# stepper_counter.net
KiCad netlist of a schematic drawn in EAGLE
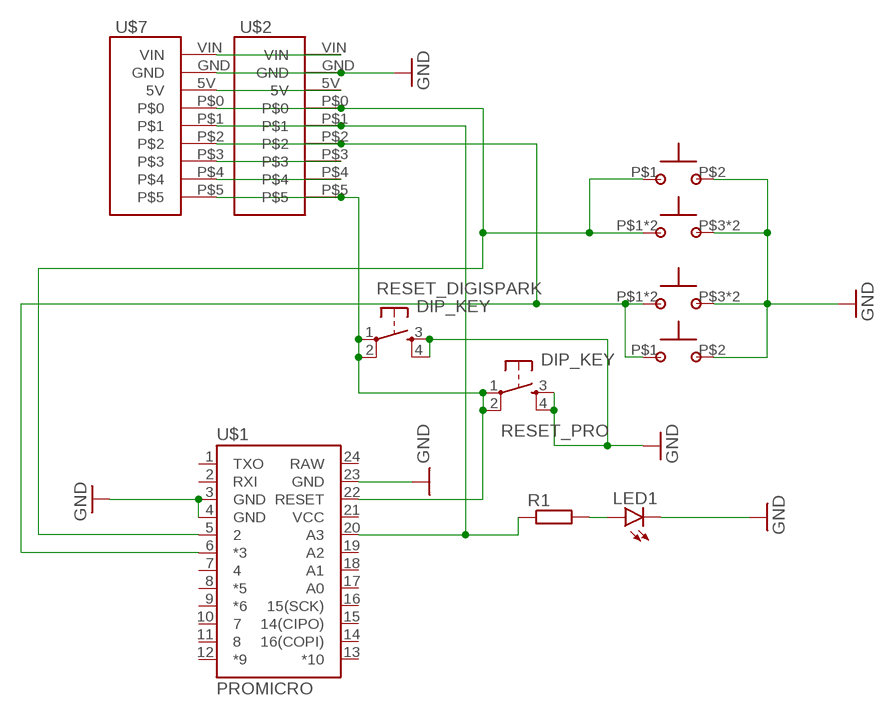
[diagram p0: schematic, sheet 1]

(export (version "E")
  (design (tool "Eeschema 10.0.6"))
  (components
    (comp (ref "LED1")
      (value "LED3MM")
      (footprint "eagle-import:LED3MM")
      (libsource (lib "eagle-import") (part "LED3MM"))
    )
    (comp (ref "R1")
      (value "R-EU_0207/10")
      (footprint "eagle-import:0207_10")
      (libsource (lib "eagle-import") (part "R-EU_0207/10"))
    )
    (comp (ref "RESET_DIGISPARK")
      (value "DIP_KEY")
      (footprint "eagle-import:B3F-10XX")
      (libsource (lib "eagle-import") (part "DIP_KEY"))
    )
    (comp (ref "RESET_PRO")
      (value "DIP_KEY")
      (footprint "eagle-import:B3F-10XX")
      (libsource (lib "eagle-import") (part "DIP_KEY"))
    )
    (comp (ref "U$1")
      (value "PROMICRO")
      (footprint "eagle-import:SPARKFUN_PRO_MICRO")
      (libsource (lib "eagle-import") (part "PROMICRO"))
    )
    (comp (ref "U$2")
      (value "DIGISPARK")
      (footprint "eagle-import:DIGISPARK")
      (libsource (lib "eagle-import") (part "DIGISPARK"))
    )
    (comp (ref "U$3")
      (value "RBS040210")
      (footprint "eagle-import:RBS040210")
      (libsource (lib "eagle-import") (part "RBS040210"))
    )
    (comp (ref "U$4")
      (value "RBS040210")
      (footprint "eagle-import:RBS040210")
      (libsource (lib "eagle-import") (part "RBS040210"))
    )
    (comp (ref "U$5")
      (value "SW20D")
      (footprint "eagle-import:SW20D")
      (libsource (lib "eagle-import") (part "SW20D"))
    )
    (comp (ref "U$6")
      (value "SW20D")
      (footprint "eagle-import:SW20D")
      (libsource (lib "eagle-import") (part "SW20D"))
    )
    (comp (ref "U$7")
      (value "DIGISPARK_USB")
      (footprint "eagle-import:DIGISPARK_USB")
      (libsource (lib "eagle-import") (part "DIGISPARK_USB"))
    )
  )
  (nets
    (net (code "1") (name "/RAW") (class "Default")
      (node (ref "U$1") (pin "24") (pinfunction "RAW_24") (pintype "power_in"))
    )
    (net (code "2") (name "/VCC") (class "Default")
      (node (ref "U$1") (pin "21") (pinfunction "VCC_21") (pintype "power_in"))
    )
    (net (code "3") (name "GND") (class "Default")
      (node (ref "LED1") (pin "K") (pinfunction "C_K") (pintype "passive"))
      (node (ref "RESET_DIGISPARK") (pin "3") (pinfunction "S_3") (pintype "passive"))
      (node (ref "RESET_DIGISPARK") (pin "4") (pinfunction "S1_4") (pintype "passive"))
      (node (ref "RESET_PRO") (pin "3") (pinfunction "S_3") (pintype "passive"))
      (node (ref "RESET_PRO") (pin "4") (pinfunction "S1_4") (pintype "passive"))
      (node (ref "U$1") (pin "23") (pinfunction "GND_23") (pintype "power_in"))
      (node (ref "U$1") (pin "3") (pinfunction "GND_3") (pintype "power_in"))
      (node (ref "U$1") (pin "4") (pinfunction "GND_4") (pintype "power_in"))
      (node (ref "U$2") (pin "GND") (pinfunction "GND_GND") (pintype "bidirectional"))
      (node (ref "U$3") (pin "P$3") (pinfunction "P$2_P$3") (pintype "bidirectional"))
      (node (ref "U$3") (pin "P$4") (pinfunction "P$2_P$4") (pintype "bidirectional"))
      (node (ref "U$4") (pin "P$3") (pinfunction "P$2_P$3") (pintype "bidirectional"))
      (node (ref "U$4") (pin "P$4") (pinfunction "P$2_P$4") (pintype "bidirectional"))
      (node (ref "U$5") (pin "P$2") (pinfunction "P$2_P$2") (pintype "bidirectional"))
      (node (ref "U$6") (pin "P$2") (pinfunction "P$2_P$2") (pintype "bidirectional"))
      (node (ref "U$7") (pin "GND") (pinfunction "GND_GND") (pintype "bidirectional"))
    )
    (net (code "4") (name "Net-(LED1-PadA)") (class "Default")
      (node (ref "LED1") (pin "A") (pinfunction "A_A") (pintype "passive"))
      (node (ref "R1") (pin "2") (pinfunction "2_2") (pintype "passive"))
    )
    (net (code "5") (name "Net-(RESET_DIGISPARK-P)") (class "Default")
      (node (ref "RESET_DIGISPARK") (pin "1") (pinfunction "P_1") (pintype "passive"))
      (node (ref "RESET_DIGISPARK") (pin "2") (pinfunction "P1_2") (pintype "passive"))
      (node (ref "RESET_PRO") (pin "1") (pinfunction "P_1") (pintype "passive"))
      (node (ref "RESET_PRO") (pin "2") (pinfunction "P1_2") (pintype "passive"))
      (node (ref "U$1") (pin "22") (pinfunction "RESET_22") (pintype "bidirectional"))
      (node (ref "U$2") (pin "P$5") (pinfunction "P$5_P$5") (pintype "bidirectional"))
      (node (ref "U$7") (pin "P$5") (pinfunction "P$5_P$5") (pintype "bidirectional"))
    )
    (net (code "6") (name "Net-(U$1-*3)") (class "Default")
      (node (ref "U$1") (pin "6") (pinfunction "*3_6") (pintype "bidirectional"))
      (node (ref "U$2") (pin "P$2") (pinfunction "P$2_P$2") (pintype "bidirectional"))
      (node (ref "U$4") (pin "P$1") (pinfunction "P$1_P$1") (pintype "bidirectional"))
      (node (ref "U$4") (pin "P$2") (pinfunction "P$1_P$2") (pintype "bidirectional"))
      (node (ref "U$6") (pin "P$1") (pinfunction "P$1_P$1") (pintype "bidirectional"))
      (node (ref "U$7") (pin "P$2") (pinfunction "P$2_P$2") (pintype "bidirectional"))
    )
    (net (code "7") (name "Net-(U$1-2)") (class "Default")
      (node (ref "U$1") (pin "5") (pinfunction "2_5") (pintype "bidirectional"))
      (node (ref "U$2") (pin "P$0") (pinfunction "P$0_P$0") (pintype "bidirectional"))
      (node (ref "U$3") (pin "P$1") (pinfunction "P$1_P$1") (pintype "bidirectional"))
      (node (ref "U$3") (pin "P$2") (pinfunction "P$1_P$2") (pintype "bidirectional"))
      (node (ref "U$5") (pin "P$1") (pinfunction "P$1_P$1") (pintype "bidirectional"))
      (node (ref "U$7") (pin "P$0") (pinfunction "P$0_P$0") (pintype "bidirectional"))
    )
    (net (code "8") (name "Net-(U$1-A3)") (class "Default")
      (node (ref "R1") (pin "1") (pinfunction "1_1") (pintype "passive"))
      (node (ref "U$1") (pin "20") (pinfunction "A3_20") (pintype "bidirectional"))
      (node (ref "U$2") (pin "P$1") (pinfunction "P$1_P$1") (pintype "bidirectional"))
      (node (ref "U$7") (pin "P$1") (pinfunction "P$1_P$1") (pintype "bidirectional"))
    )
    (net (code "9") (name "Net-(U$2-Pad5V)") (class "Default")
      (node (ref "U$2") (pin "5V") (pinfunction "5V_5V") (pintype "bidirectional"))
      (node (ref "U$7") (pin "5V") (pinfunction "5V_5V") (pintype "bidirectional"))
    )
    (net (code "10") (name "Net-(U$2-PadP$3)") (class "Default")
      (node (ref "U$2") (pin "P$3") (pinfunction "P$3_P$3") (pintype "bidirectional"))
      (node (ref "U$7") (pin "P$3") (pinfunction "P$3_P$3") (pintype "bidirectional"))
    )
    (net (code "11") (name "Net-(U$2-PadP$4)") (class "Default")
      (node (ref "U$2") (pin "P$4") (pinfunction "P$4_P$4") (pintype "bidirectional"))
      (node (ref "U$7") (pin "P$4") (pinfunction "P$4_P$4") (pintype "bidirectional"))
    )
    (net (code "12") (name "Net-(U$2-PadVIN)") (class "Default")
      (node (ref "U$2") (pin "VIN") (pinfunction "VIN_VIN") (pintype "bidirectional"))
      (node (ref "U$7") (pin "VIN") (pinfunction "VIN_VIN") (pintype "bidirectional"))
    )
    (net (code "13") (name "unconnected-(U$1-*5-Pad8)") (class "Default")
      (node (ref "U$1") (pin "8") (pinfunction "*5_8") (pintype "bidirectional"))
    )
    (net (code "14") (name "unconnected-(U$1-*6-Pad9)") (class "Default")
      (node (ref "U$1") (pin "9") (pinfunction "*6_9") (pintype "bidirectional"))
    )
    (net (code "15") (name "unconnected-(U$1-*9-Pad12)") (class "Default")
      (node (ref "U$1") (pin "12") (pinfunction "*9_12") (pintype "bidirectional"))
    )
    (net (code "16") (name "unconnected-(U$1-*10-Pad13)") (class "Default")
      (node (ref "U$1") (pin "13") (pinfunction "*10_13") (pintype "bidirectional"))
    )
    (net (code "17") (name "unconnected-(U$1-4-Pad7)") (class "Default")
      (node (ref "U$1") (pin "7") (pinfunction "4_7") (pintype "bidirectional"))
    )
    (net (code "18") (name "unconnected-(U$1-7-Pad10)") (class "Default")
      (node (ref "U$1") (pin "10") (pinfunction "7_10") (pintype "bidirectional"))
    )
    (net (code "19") (name "unconnected-(U$1-8-Pad11)") (class "Default")
      (node (ref "U$1") (pin "11") (pinfunction "8_11") (pintype "bidirectional"))
    )
    (net (code "20") (name "unconnected-(U$1-14(CIPO)-Pad15)") (class "Default")
      (node (ref "U$1") (pin "15") (pinfunction "14(CIPO)_15") (pintype "bidirectional"))
    )
    (net (code "21") (name "unconnected-(U$1-15(SCK)-Pad16)") (class "Default")
      (node (ref "U$1") (pin "16") (pinfunction "15(SCK)_16") (pintype "bidirectional"))
    )
    (net (code "22") (name "unconnected-(U$1-16(COPI)-Pad14)") (class "Default")
      (node (ref "U$1") (pin "14") (pinfunction "16(COPI)_14") (pintype "bidirectional"))
    )
    (net (code "23") (name "unconnected-(U$1-A0-Pad17)") (class "Default")
      (node (ref "U$1") (pin "17") (pinfunction "A0_17") (pintype "bidirectional"))
    )
    (net (code "24") (name "unconnected-(U$1-A1-Pad18)") (class "Default")
      (node (ref "U$1") (pin "18") (pinfunction "A1_18") (pintype "bidirectional"))
    )
    (net (code "25") (name "unconnected-(U$1-A2-Pad19)") (class "Default")
      (node (ref "U$1") (pin "19") (pinfunction "A2_19") (pintype "bidirectional"))
    )
    (net (code "26") (name "unconnected-(U$1-RXI-Pad2)") (class "Default")
      (node (ref "U$1") (pin "2") (pinfunction "RXI_2") (pintype "bidirectional"))
    )
    (net (code "27") (name "unconnected-(U$1-TXO-Pad1)") (class "Default")
      (node (ref "U$1") (pin "1") (pinfunction "TXO_1") (pintype "bidirectional"))
    )
  )
)
